# fernsteuerung.net
KiCad netlist of a schematic drawn in EAGLE
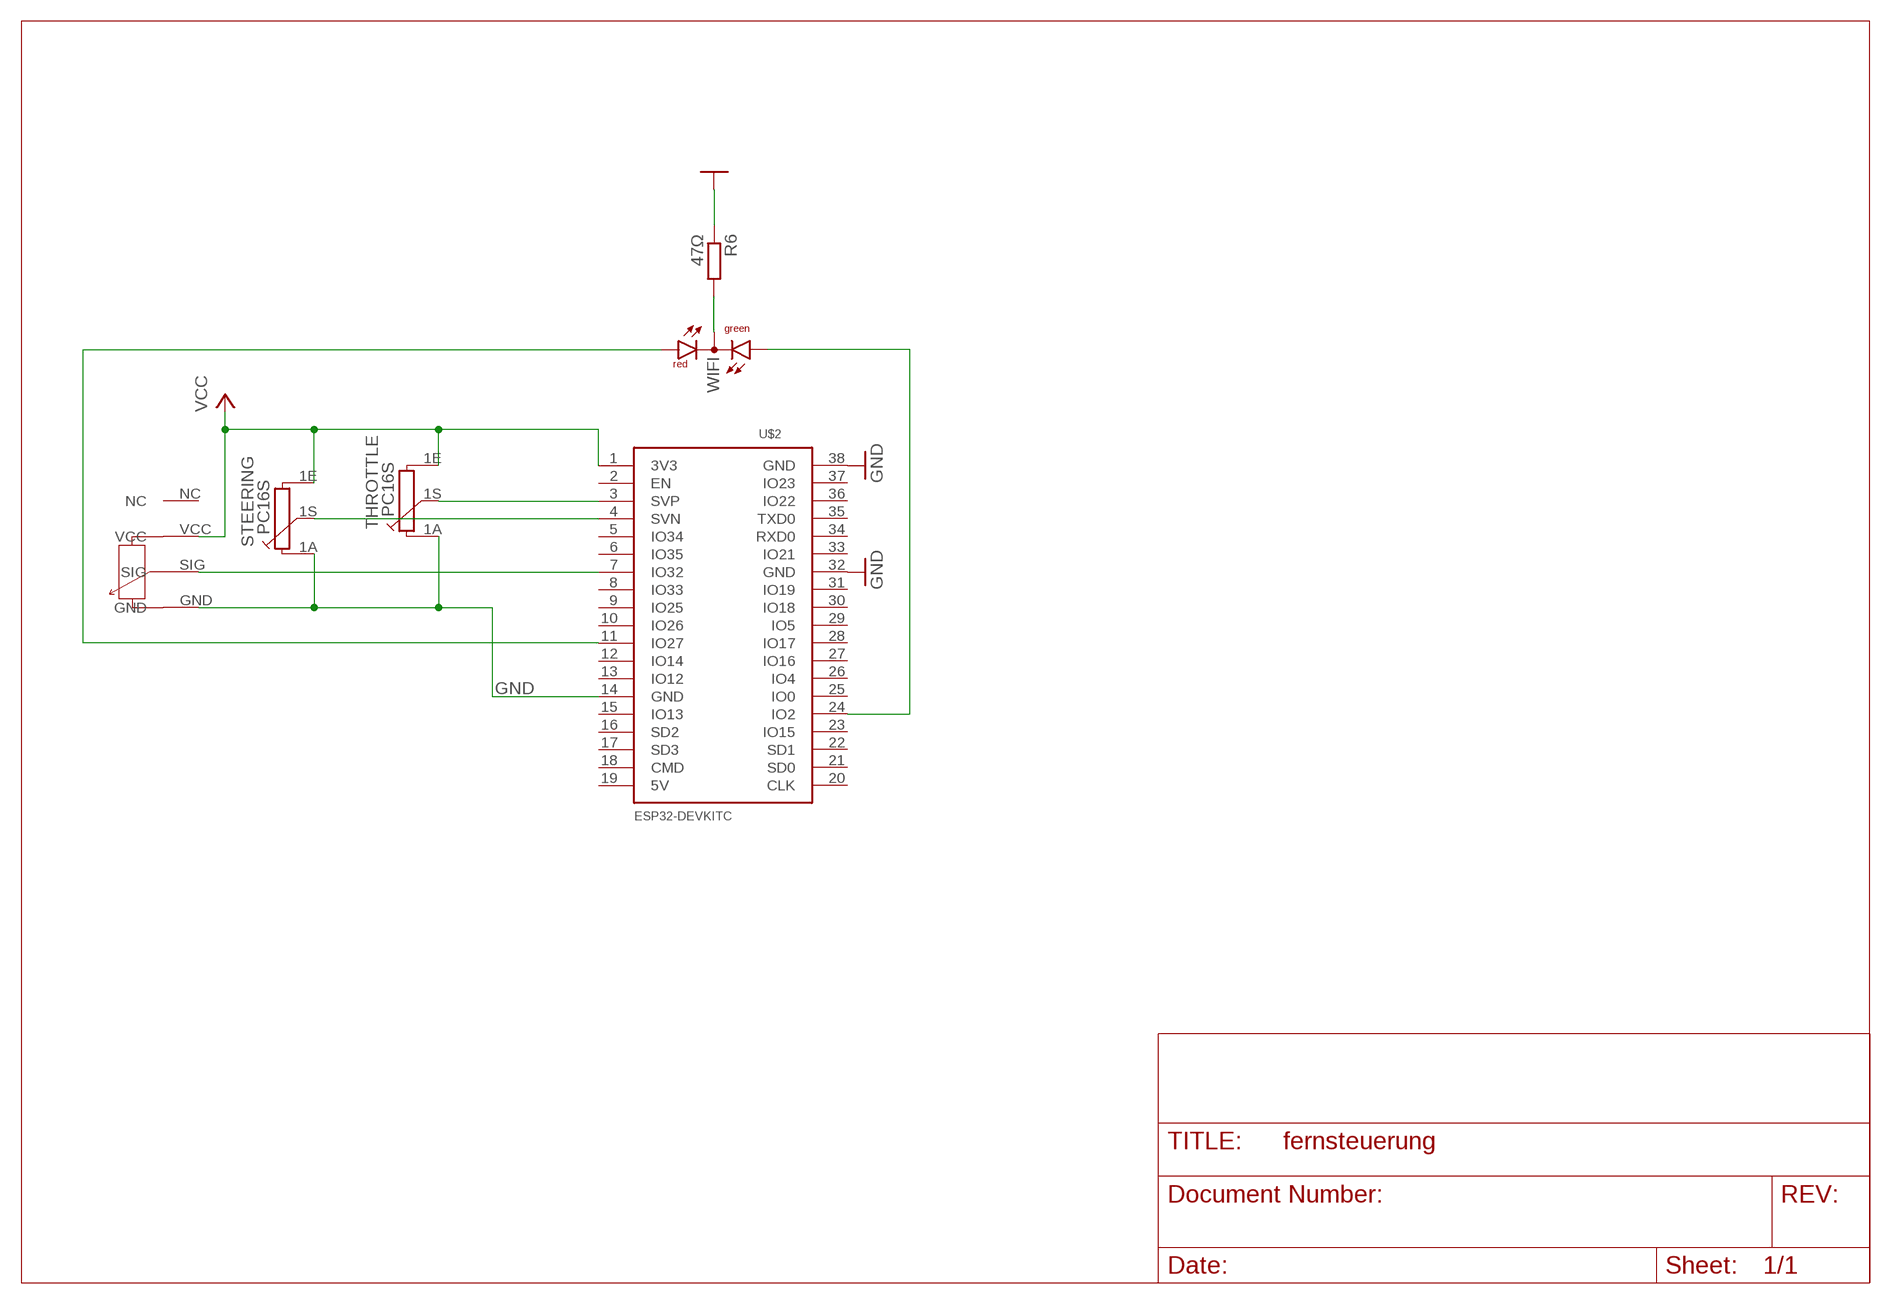
[diagram p0: schematic, sheet 1]

(export (version "E")
  (design (tool "Eeschema 10.0.6"))
  (components
    (comp (ref "R6")
      (value "47Ω")
      (footprint "eagle-import:R0603")
      (libsource (lib "eagle-import") (part "R-EU_R0603"))
    )
    (comp (ref "STEERING")
      (value "PC16S")
      (footprint "eagle-import:PC16S")
      (libsource (lib "eagle-import") (part "PC16S"))
    )
    (comp (ref "THROTTLE")
      (value "PC16S")
      (footprint "eagle-import:PC16S")
      (libsource (lib "eagle-import") (part "PC16S"))
    )
    (comp (ref "TRIM")
      (value "ALPS_RK11K")
      (footprint "eagle-import:ALPS_RK11K")
      (libsource (lib "eagle-import") (part "ALPS_RK11K"))
    )
    (comp (ref "U$2")
      (value "ESP32DEVKITC")
      (footprint "eagle-import:ESP32-DEVKITC")
      (libsource (lib "eagle-import") (part "ESP32DEVKITC"))
    )
    (comp (ref "WIFI")
      (value "DUOLED-RG-C3MM")
      (footprint "eagle-import:DUOLED-A-3MM")
      (libsource (lib "eagle-import") (part "DUOLED-RG-C3MM"))
    )
  )
  (nets
    (net (code "1") (name "GND") (class "Default")
      (node (ref "R6") (pin "1") (pinfunction "1_1") (pintype "passive"))
      (node (ref "STEERING") (pin "1A") (pinfunction "1A_1A") (pintype "passive"))
      (node (ref "THROTTLE") (pin "1A") (pinfunction "1A_1A") (pintype "passive"))
      (node (ref "TRIM") (pin "GND") (pinfunction "GND_GND") (pintype "bidirectional"))
      (node (ref "U$2") (pin "14") (pinfunction "GND_14") (pintype "bidirectional"))
      (node (ref "U$2") (pin "32") (pinfunction "GND_32") (pintype "bidirectional"))
      (node (ref "U$2") (pin "38") (pinfunction "GND_38") (pintype "bidirectional"))
    )
    (net (code "2") (name "Net-(U$2-IO2)") (class "Default")
      (node (ref "U$2") (pin "24") (pinfunction "IO2_24") (pintype "bidirectional"))
      (node (ref "WIFI") (pin "1") (pinfunction "AG_1") (pintype "passive"))
    )
    (net (code "3") (name "Net-(U$2-IO27)") (class "Default")
      (node (ref "U$2") (pin "11") (pinfunction "IO27_11") (pintype "bidirectional"))
      (node (ref "WIFI") (pin "3") (pinfunction "AR_3") (pintype "passive"))
    )
    (net (code "4") (name "Net-(U$2-IO32)") (class "Default")
      (node (ref "TRIM") (pin "SIG") (pinfunction "SIG_SIG") (pintype "bidirectional"))
      (node (ref "U$2") (pin "7") (pinfunction "IO32_7") (pintype "bidirectional"))
    )
    (net (code "5") (name "Net-(U$2-SVN)") (class "Default")
      (node (ref "STEERING") (pin "1S") (pinfunction "1S_1S") (pintype "passive"))
      (node (ref "U$2") (pin "4") (pinfunction "SVN_4") (pintype "bidirectional"))
    )
    (net (code "6") (name "Net-(U$2-SVP)") (class "Default")
      (node (ref "THROTTLE") (pin "1S") (pinfunction "1S_1S") (pintype "passive"))
      (node (ref "U$2") (pin "3") (pinfunction "SVP_3") (pintype "bidirectional"))
    )
    (net (code "7") (name "Net-(WIFI-C)") (class "Default")
      (node (ref "R6") (pin "2") (pinfunction "2_2") (pintype "passive"))
      (node (ref "WIFI") (pin "2") (pinfunction "C_2") (pintype "passive"))
    )
    (net (code "8") (name "VCC") (class "Default")
      (node (ref "STEERING") (pin "1E") (pinfunction "1E_1E") (pintype "passive"))
      (node (ref "THROTTLE") (pin "1E") (pinfunction "1E_1E") (pintype "passive"))
      (node (ref "TRIM") (pin "VCC") (pinfunction "VCC_VCC") (pintype "bidirectional"))
      (node (ref "U$2") (pin "1") (pinfunction "3V3_1") (pintype "bidirectional"))
    )
    (net (code "9") (name "unconnected-(TRIM-PadNC)") (class "Default")
      (node (ref "TRIM") (pin "NC") (pinfunction "NC_NC") (pintype "bidirectional"))
    )
    (net (code "10") (name "unconnected-(U$2-5V-Pad19)") (class "Default")
      (node (ref "U$2") (pin "19") (pinfunction "5V_19") (pintype "bidirectional"))
    )
    (net (code "11") (name "unconnected-(U$2-CLK-Pad20)") (class "Default")
      (node (ref "U$2") (pin "20") (pinfunction "CLK_20") (pintype "bidirectional"))
    )
    (net (code "12") (name "unconnected-(U$2-CMD-Pad18)") (class "Default")
      (node (ref "U$2") (pin "18") (pinfunction "CMD_18") (pintype "bidirectional"))
    )
    (net (code "13") (name "unconnected-(U$2-EN-Pad2)") (class "Default")
      (node (ref "U$2") (pin "2") (pinfunction "EN_2") (pintype "bidirectional"))
    )
    (net (code "14") (name "unconnected-(U$2-IO0-Pad25)") (class "Default")
      (node (ref "U$2") (pin "25") (pinfunction "IO0_25") (pintype "bidirectional"))
    )
    (net (code "15") (name "unconnected-(U$2-IO4-Pad26)") (class "Default")
      (node (ref "U$2") (pin "26") (pinfunction "IO4_26") (pintype "bidirectional"))
    )
    (net (code "16") (name "unconnected-(U$2-IO5-Pad29)") (class "Default")
      (node (ref "U$2") (pin "29") (pinfunction "IO5_29") (pintype "bidirectional"))
    )
    (net (code "17") (name "unconnected-(U$2-IO12-Pad13)") (class "Default")
      (node (ref "U$2") (pin "13") (pinfunction "IO12_13") (pintype "bidirectional"))
    )
    (net (code "18") (name "unconnected-(U$2-IO13-Pad15)") (class "Default")
      (node (ref "U$2") (pin "15") (pinfunction "IO13_15") (pintype "bidirectional"))
    )
    (net (code "19") (name "unconnected-(U$2-IO14-Pad12)") (class "Default")
      (node (ref "U$2") (pin "12") (pinfunction "IO14_12") (pintype "bidirectional"))
    )
    (net (code "20") (name "unconnected-(U$2-IO15-Pad23)") (class "Default")
      (node (ref "U$2") (pin "23") (pinfunction "IO15_23") (pintype "bidirectional"))
    )
    (net (code "21") (name "unconnected-(U$2-IO16-Pad27)") (class "Default")
      (node (ref "U$2") (pin "27") (pinfunction "IO16_27") (pintype "bidirectional"))
    )
    (net (code "22") (name "unconnected-(U$2-IO17-Pad28)") (class "Default")
      (node (ref "U$2") (pin "28") (pinfunction "IO17_28") (pintype "bidirectional"))
    )
    (net (code "23") (name "unconnected-(U$2-IO18-Pad30)") (class "Default")
      (node (ref "U$2") (pin "30") (pinfunction "IO18_30") (pintype "bidirectional"))
    )
    (net (code "24") (name "unconnected-(U$2-IO19-Pad31)") (class "Default")
      (node (ref "U$2") (pin "31") (pinfunction "IO19_31") (pintype "bidirectional"))
    )
    (net (code "25") (name "unconnected-(U$2-IO21-Pad33)") (class "Default")
      (node (ref "U$2") (pin "33") (pinfunction "IO21_33") (pintype "bidirectional"))
    )
    (net (code "26") (name "unconnected-(U$2-IO22-Pad36)") (class "Default")
      (node (ref "U$2") (pin "36") (pinfunction "IO22_36") (pintype "bidirectional"))
    )
    (net (code "27") (name "unconnected-(U$2-IO23-Pad37)") (class "Default")
      (node (ref "U$2") (pin "37") (pinfunction "IO23_37") (pintype "bidirectional"))
    )
    (net (code "28") (name "unconnected-(U$2-IO25-Pad9)") (class "Default")
      (node (ref "U$2") (pin "9") (pinfunction "IO25_9") (pintype "bidirectional"))
    )
    (net (code "29") (name "unconnected-(U$2-IO26-Pad10)") (class "Default")
      (node (ref "U$2") (pin "10") (pinfunction "IO26_10") (pintype "bidirectional"))
    )
    (net (code "30") (name "unconnected-(U$2-IO33-Pad8)") (class "Default")
      (node (ref "U$2") (pin "8") (pinfunction "IO33_8") (pintype "bidirectional"))
    )
    (net (code "31") (name "unconnected-(U$2-IO34-Pad5)") (class "Default")
      (node (ref "U$2") (pin "5") (pinfunction "IO34_5") (pintype "bidirectional"))
    )
    (net (code "32") (name "unconnected-(U$2-IO35-Pad6)") (class "Default")
      (node (ref "U$2") (pin "6") (pinfunction "IO35_6") (pintype "bidirectional"))
    )
    (net (code "33") (name "unconnected-(U$2-RXD0-Pad34)") (class "Default")
      (node (ref "U$2") (pin "34") (pinfunction "RXD0_34") (pintype "bidirectional"))
    )
    (net (code "34") (name "unconnected-(U$2-SD0-Pad21)") (class "Default")
      (node (ref "U$2") (pin "21") (pinfunction "SD0_21") (pintype "bidirectional"))
    )
    (net (code "35") (name "unconnected-(U$2-SD1-Pad22)") (class "Default")
      (node (ref "U$2") (pin "22") (pinfunction "SD1_22") (pintype "bidirectional"))
    )
    (net (code "36") (name "unconnected-(U$2-SD2-Pad16)") (class "Default")
      (node (ref "U$2") (pin "16") (pinfunction "SD2_16") (pintype "bidirectional"))
    )
    (net (code "37") (name "unconnected-(U$2-SD3-Pad17)") (class "Default")
      (node (ref "U$2") (pin "17") (pinfunction "SD3_17") (pintype "bidirectional"))
    )
    (net (code "38") (name "unconnected-(U$2-TXD0-Pad35)") (class "Default")
      (node (ref "U$2") (pin "35") (pinfunction "TXD0_35") (pintype "bidirectional"))
    )
  )
)
